# Nusbio_2-FT4222.net
KiCad netlist of a schematic drawn in EAGLE
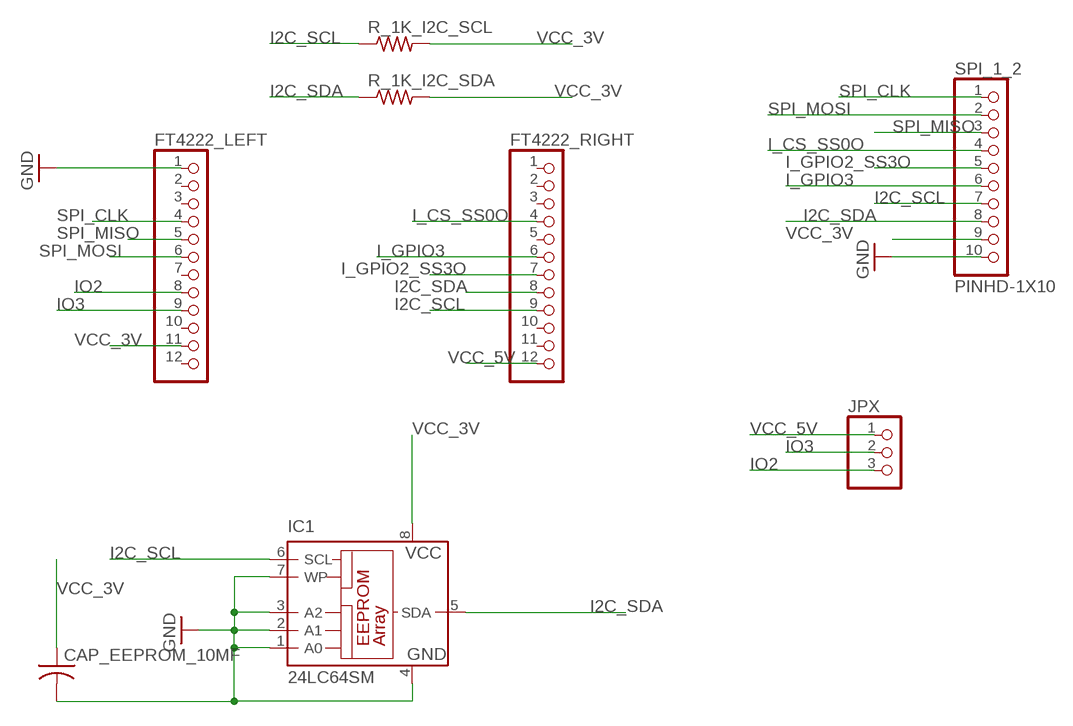
[diagram p0: schematic, sheet 1]

(export (version "E")
  (design (tool "Eeschema 10.0.6"))
  (components
    (comp (ref "CAP_EEPROM_10MF")
      (value "C-USC1206")
      (footprint "eagle-import:C1206")
      (libsource (lib "eagle-import") (part "C-USC1206"))
    )
    (comp (ref "FT4222_LEFT")
      (value "PINHD-1X12")
      (footprint "eagle-import:1X12")
      (libsource (lib "eagle-import") (part "PINHD-1X12"))
    )
    (comp (ref "FT4222_RIGHT")
      (value "PINHD-1X12")
      (footprint "eagle-import:1X12")
      (libsource (lib "eagle-import") (part "PINHD-1X12"))
    )
    (comp (ref "IC1")
      (value "24LC64SM")
      (footprint "eagle-import:SO-08M")
      (fields (field (name "MF") "MICROCHIP") (field (name "MPN") "24LC64T-I/SN"))
      (libsource (lib "eagle-import") (part "24SMLC64"))
    )
    (comp (ref "JPX")
      (value "PINHD-1X3")
      (footprint "eagle-import:1X03")
      (libsource (lib "eagle-import") (part "PINHD-1X3"))
    )
    (comp (ref "R_1K_I2C_SCL")
      (value "R-US_R1206")
      (footprint "eagle-import:R1206")
      (libsource (lib "eagle-import") (part "R-US_R1206"))
    )
    (comp (ref "R_1K_I2C_SDA")
      (value "R-US_R1206")
      (footprint "eagle-import:R1206")
      (libsource (lib "eagle-import") (part "R-US_R1206"))
    )
    (comp (ref "SPI_1_2")
      (value "PINHD-1X10")
      (footprint "eagle-import:1X10-BIG")
      (libsource (lib "eagle-import") (part "PINHD-1X10"))
    )
  )
  (nets
    (net (code "1") (name "/I2C_SCL") (class "Default")
      (node (ref "FT4222_RIGHT") (pin "9") (pinfunction "9_9") (pintype "passive"))
      (node (ref "IC1") (pin "6") (pinfunction "SCL_6") (pintype "input"))
      (node (ref "R_1K_I2C_SCL") (pin "1") (pinfunction "1_1") (pintype "passive"))
      (node (ref "SPI_1_2") (pin "7") (pinfunction "7_7") (pintype "passive"))
    )
    (net (code "2") (name "/I2C_SDA") (class "Default")
      (node (ref "FT4222_RIGHT") (pin "8") (pinfunction "8_8") (pintype "passive"))
      (node (ref "IC1") (pin "5") (pinfunction "SDA_5") (pintype "bidirectional"))
      (node (ref "R_1K_I2C_SDA") (pin "1") (pinfunction "1_1") (pintype "passive"))
      (node (ref "SPI_1_2") (pin "8") (pinfunction "8_8") (pintype "passive"))
    )
    (net (code "3") (name "/IO2") (class "Default")
      (node (ref "FT4222_LEFT") (pin "8") (pinfunction "8_8") (pintype "passive"))
      (node (ref "JPX") (pin "3") (pinfunction "3_3") (pintype "passive"))
    )
    (net (code "4") (name "/IO3") (class "Default")
      (node (ref "FT4222_LEFT") (pin "9") (pinfunction "9_9") (pintype "passive"))
      (node (ref "JPX") (pin "2") (pinfunction "2_2") (pintype "passive"))
    )
    (net (code "5") (name "/I_CS_SS0O") (class "Default")
      (node (ref "FT4222_RIGHT") (pin "4") (pinfunction "4_4") (pintype "passive"))
      (node (ref "SPI_1_2") (pin "4") (pinfunction "4_4") (pintype "passive"))
    )
    (net (code "6") (name "/I_GPIO2_SS3O") (class "Default")
      (node (ref "FT4222_RIGHT") (pin "7") (pinfunction "7_7") (pintype "passive"))
      (node (ref "SPI_1_2") (pin "5") (pinfunction "5_5") (pintype "passive"))
    )
    (net (code "7") (name "/I_GPIO3") (class "Default")
      (node (ref "FT4222_RIGHT") (pin "6") (pinfunction "6_6") (pintype "passive"))
      (node (ref "SPI_1_2") (pin "6") (pinfunction "6_6") (pintype "passive"))
    )
    (net (code "8") (name "/SPI_CLK") (class "Default")
      (node (ref "FT4222_LEFT") (pin "4") (pinfunction "4_4") (pintype "passive"))
      (node (ref "SPI_1_2") (pin "1") (pinfunction "1_1") (pintype "passive"))
    )
    (net (code "9") (name "/SPI_MISO") (class "Default")
      (node (ref "FT4222_LEFT") (pin "5") (pinfunction "5_5") (pintype "passive"))
      (node (ref "SPI_1_2") (pin "3") (pinfunction "3_3") (pintype "passive"))
    )
    (net (code "10") (name "/SPI_MOSI") (class "Default")
      (node (ref "FT4222_LEFT") (pin "6") (pinfunction "6_6") (pintype "passive"))
      (node (ref "SPI_1_2") (pin "2") (pinfunction "2_2") (pintype "passive"))
    )
    (net (code "11") (name "/VCC_3V") (class "Default")
      (node (ref "CAP_EEPROM_10MF") (pin "1") (pinfunction "1_1") (pintype "passive"))
      (node (ref "FT4222_LEFT") (pin "11") (pinfunction "11_11") (pintype "passive"))
      (node (ref "IC1") (pin "8") (pinfunction "VCC_8") (pintype "power_in"))
      (node (ref "R_1K_I2C_SCL") (pin "2") (pinfunction "2_2") (pintype "passive"))
      (node (ref "R_1K_I2C_SDA") (pin "2") (pinfunction "2_2") (pintype "passive"))
      (node (ref "SPI_1_2") (pin "9") (pinfunction "9_9") (pintype "passive"))
    )
    (net (code "12") (name "/VCC_5V") (class "Default")
      (node (ref "FT4222_RIGHT") (pin "12") (pinfunction "12_12") (pintype "passive"))
      (node (ref "JPX") (pin "1") (pinfunction "1_1") (pintype "passive"))
    )
    (net (code "13") (name "GND") (class "Default")
      (node (ref "CAP_EEPROM_10MF") (pin "2") (pinfunction "2_2") (pintype "passive"))
      (node (ref "FT4222_LEFT") (pin "1") (pinfunction "1_1") (pintype "passive"))
      (node (ref "IC1") (pin "1") (pinfunction "A0_1") (pintype "input"))
      (node (ref "IC1") (pin "2") (pinfunction "A1_2") (pintype "input"))
      (node (ref "IC1") (pin "3") (pinfunction "A2_3") (pintype "input"))
      (node (ref "IC1") (pin "4") (pinfunction "GND_4") (pintype "power_in"))
      (node (ref "IC1") (pin "7") (pinfunction "WP_7") (pintype "input"))
      (node (ref "SPI_1_2") (pin "10") (pinfunction "10_10") (pintype "passive"))
    )
    (net (code "14") (name "unconnected-(FT4222_LEFT-Pad2)") (class "Default")
      (node (ref "FT4222_LEFT") (pin "2") (pinfunction "2_2") (pintype "passive"))
    )
    (net (code "15") (name "unconnected-(FT4222_LEFT-Pad3)") (class "Default")
      (node (ref "FT4222_LEFT") (pin "3") (pinfunction "3_3") (pintype "passive"))
    )
    (net (code "16") (name "unconnected-(FT4222_LEFT-Pad7)") (class "Default")
      (node (ref "FT4222_LEFT") (pin "7") (pinfunction "7_7") (pintype "passive"))
    )
    (net (code "17") (name "unconnected-(FT4222_LEFT-Pad10)") (class "Default")
      (node (ref "FT4222_LEFT") (pin "10") (pinfunction "10_10") (pintype "passive"))
    )
    (net (code "18") (name "unconnected-(FT4222_LEFT-Pad12)") (class "Default")
      (node (ref "FT4222_LEFT") (pin "12") (pinfunction "12_12") (pintype "passive"))
    )
    (net (code "19") (name "unconnected-(FT4222_RIGHT-Pad1)") (class "Default")
      (node (ref "FT4222_RIGHT") (pin "1") (pinfunction "1_1") (pintype "passive"))
    )
    (net (code "20") (name "unconnected-(FT4222_RIGHT-Pad2)") (class "Default")
      (node (ref "FT4222_RIGHT") (pin "2") (pinfunction "2_2") (pintype "passive"))
    )
    (net (code "21") (name "unconnected-(FT4222_RIGHT-Pad3)") (class "Default")
      (node (ref "FT4222_RIGHT") (pin "3") (pinfunction "3_3") (pintype "passive"))
    )
    (net (code "22") (name "unconnected-(FT4222_RIGHT-Pad5)") (class "Default")
      (node (ref "FT4222_RIGHT") (pin "5") (pinfunction "5_5") (pintype "passive"))
    )
    (net (code "23") (name "unconnected-(FT4222_RIGHT-Pad10)") (class "Default")
      (node (ref "FT4222_RIGHT") (pin "10") (pinfunction "10_10") (pintype "passive"))
    )
    (net (code "24") (name "unconnected-(FT4222_RIGHT-Pad11)") (class "Default")
      (node (ref "FT4222_RIGHT") (pin "11") (pinfunction "11_11") (pintype "passive"))
    )
  )
)
